# WaterSensor-V01-Build014.net
KiCad netlist of a schematic drawn in EAGLE
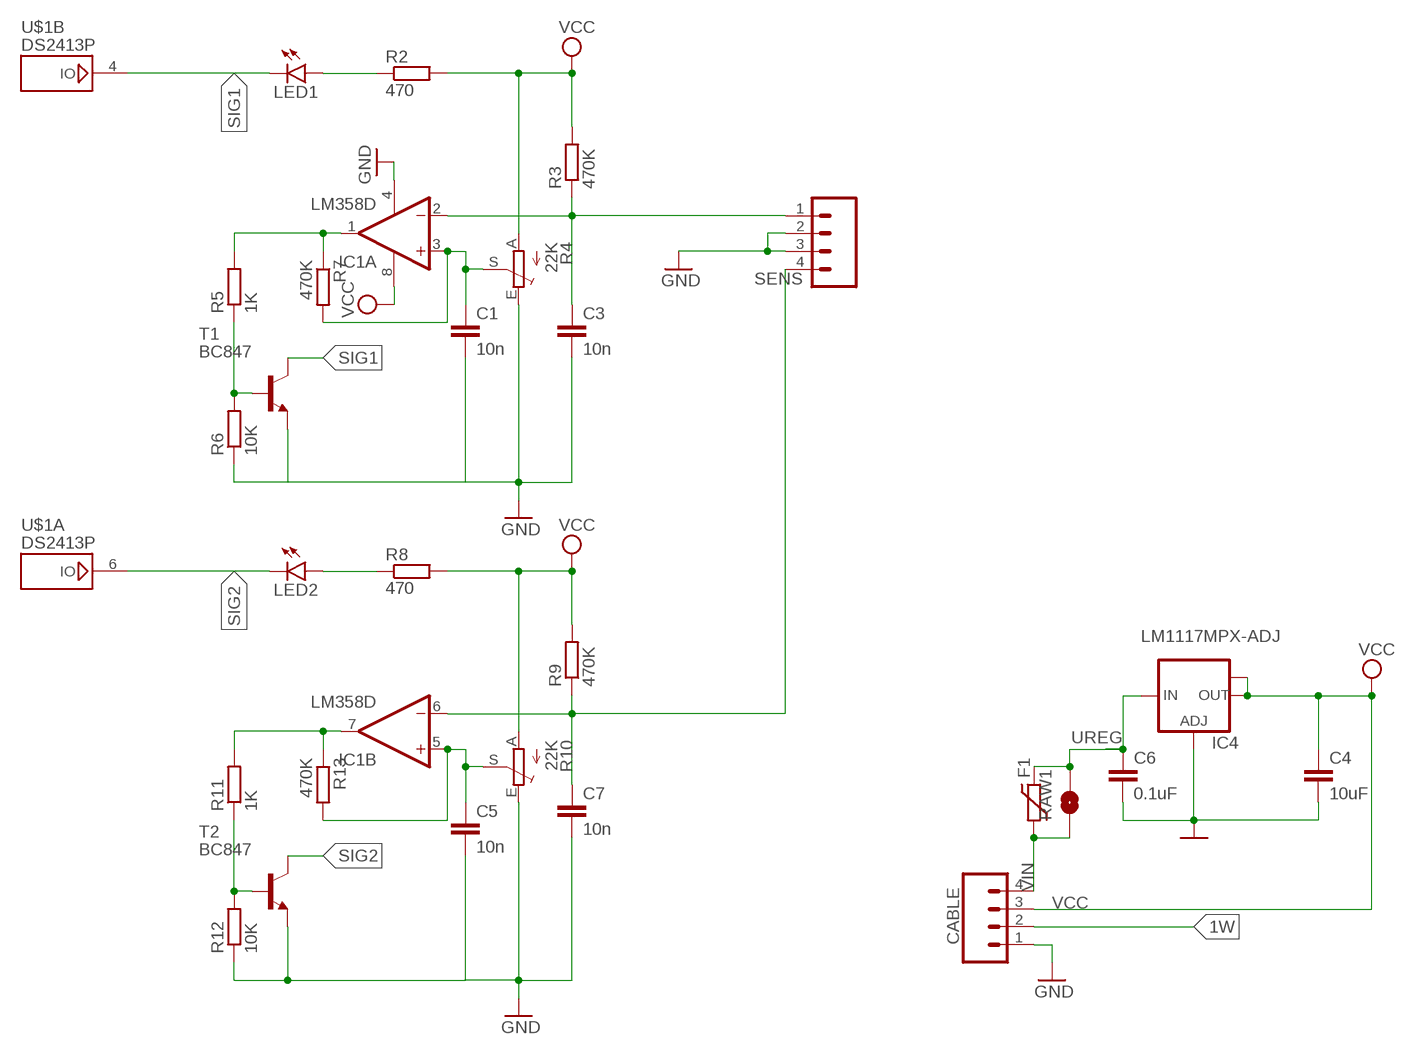
[diagram p0: schematic, sheet 1]

(export (version "E")
  (design (tool "Eeschema 10.0.6"))
  (components
    (comp (ref "C1")
      (value "10n")
      (footprint "eagle-import:C0805K")
      (libsource (lib "eagle-import") (part "rcl_334_C-EUC0805K"))
    )
    (comp (ref "C3")
      (value "10n")
      (footprint "eagle-import:C0805K")
      (libsource (lib "eagle-import") (part "rcl_334_C-EUC0805K"))
    )
    (comp (ref "C4")
      (value "10uF")
      (footprint "eagle-import:C1210")
      (libsource (lib "eagle-import") (part "C-EUC1210"))
    )
    (comp (ref "C5")
      (value "10n")
      (footprint "eagle-import:C0805K")
      (libsource (lib "eagle-import") (part "rcl_334_C-EUC0805K"))
    )
    (comp (ref "C6")
      (value "0.1uF")
      (footprint "eagle-import:C1206")
      (libsource (lib "eagle-import") (part "C-EUC1206"))
    )
    (comp (ref "C7")
      (value "10n")
      (footprint "eagle-import:C0805K")
      (libsource (lib "eagle-import") (part "rcl_334_C-EUC0805K"))
    )
    (comp (ref "CABLE")
      (value "CONN_04LONGPADS")
      (footprint "eagle-import:1X04_LONGPADS")
      (libsource (lib "eagle-import") (part "CONN_04LONGPADS"))
    )
    (comp (ref "F1")
      (value "1812L")
      (footprint "eagle-import:1812L")
      (libsource (lib "eagle-import") (part "1812L"))
    )
    (comp (ref "IC1")
      (value "LM358D")
      (footprint "eagle-import:SO08")
      (libsource (lib "eagle-import") (part "LM358D"))
    )
    (comp (ref "IC4")
      (value "LM1117MPX-ADJ")
      (footprint "eagle-import:SOT223")
      (libsource (lib "eagle-import") (part "LM1117MPX-ADJ"))
    )
    (comp (ref "LED1")
      (value "LEDCHIP-LED0805")
      (footprint "eagle-import:CHIP-LED0805")
      (libsource (lib "eagle-import") (part "LEDCHIP-LED0805"))
    )
    (comp (ref "LED2")
      (value "LEDCHIP-LED0805")
      (footprint "eagle-import:CHIP-LED0805")
      (libsource (lib "eagle-import") (part "LEDCHIP-LED0805"))
    )
    (comp (ref "R2")
      (value "470")
      (footprint "eagle-import:R0805W")
      (libsource (lib "eagle-import") (part "R-EU_R0805W"))
    )
    (comp (ref "R3")
      (value "470K")
      (footprint "eagle-import:R0805W")
      (libsource (lib "eagle-import") (part "R-EU_R0805W"))
    )
    (comp (ref "R4")
      (value "22K")
      (footprint "eagle-import:CA6V")
      (libsource (lib "eagle-import") (part "TRIM_EU-CA6V"))
    )
    (comp (ref "R5")
      (value "1K")
      (footprint "eagle-import:R0805W")
      (libsource (lib "eagle-import") (part "R-EU_R0805W"))
    )
    (comp (ref "R6")
      (value "10K")
      (footprint "eagle-import:R0805W")
      (libsource (lib "eagle-import") (part "R-EU_R0805W"))
    )
    (comp (ref "R7")
      (value "470K")
      (footprint "eagle-import:R0805W")
      (libsource (lib "eagle-import") (part "R-EU_R0805W"))
    )
    (comp (ref "R8")
      (value "470")
      (footprint "eagle-import:R0805W")
      (libsource (lib "eagle-import") (part "R-EU_R0805W"))
    )
    (comp (ref "R9")
      (value "470K")
      (footprint "eagle-import:R0805W")
      (libsource (lib "eagle-import") (part "R-EU_R0805W"))
    )
    (comp (ref "R10")
      (value "22K")
      (footprint "eagle-import:CA6V")
      (libsource (lib "eagle-import") (part "TRIM_EU-CA6V"))
    )
    (comp (ref "R11")
      (value "1K")
      (footprint "eagle-import:R0805W")
      (libsource (lib "eagle-import") (part "R-EU_R0805W"))
    )
    (comp (ref "R12")
      (value "10K")
      (footprint "eagle-import:R0805W")
      (libsource (lib "eagle-import") (part "R-EU_R0805W"))
    )
    (comp (ref "R13")
      (value "470K")
      (footprint "eagle-import:R0805W")
      (libsource (lib "eagle-import") (part "R-EU_R0805W"))
    )
    (comp (ref "RAW1")
      (value "JUMPER-SMT_2_NO_SILK")
      (footprint "eagle-import:SMT-JUMPER_2_NO_SILK")
      (libsource (lib "eagle-import") (part "JUMPER-SMT_2_NO_SILK"))
    )
    (comp (ref "SENS")
      (value "CONN_04LONGPADS")
      (footprint "eagle-import:1X04_LONGPADS")
      (libsource (lib "eagle-import") (part "CONN_04LONGPADS"))
    )
    (comp (ref "T1")
      (value "BC847")
      (footprint "eagle-import:SOT23")
      (libsource (lib "eagle-import") (part "BC847"))
    )
    (comp (ref "T2")
      (value "BC847")
      (footprint "eagle-import:SOT23")
      (libsource (lib "eagle-import") (part "BC847"))
    )
    (comp (ref "U$1")
      (value "DS2413P")
      (footprint "eagle-import:TSOC6")
      (libsource (lib "eagle-import") (part "DS2413P"))
    )
  )
  (nets
    (net (code "1") (name "/UREG") (class "Default")
      (node (ref "C6") (pin "1") (pinfunction "1_1") (pintype "passive"))
      (node (ref "F1") (pin "P$1") (pinfunction "1_P$1") (pintype "passive"))
      (node (ref "IC4") (pin "3") (pinfunction "IN_3") (pintype "input"))
      (node (ref "RAW1") (pin "2") (pinfunction "2_2") (pintype "passive"))
    )
    (net (code "2") (name "/VIN") (class "Default")
      (node (ref "CABLE") (pin "4") (pinfunction "4_4") (pintype "passive"))
      (node (ref "F1") (pin "P$2") (pinfunction "2_P$2") (pintype "passive"))
      (node (ref "RAW1") (pin "1") (pinfunction "1_1") (pintype "passive"))
    )
    (net (code "3") (name "1W") (class "Default")
      (node (ref "CABLE") (pin "2") (pinfunction "2_2") (pintype "passive"))
    )
    (net (code "4") (name "GND") (class "Default")
      (node (ref "C1") (pin "2") (pinfunction "2_2") (pintype "passive"))
      (node (ref "C3") (pin "2") (pinfunction "2_2") (pintype "passive"))
      (node (ref "C4") (pin "2") (pinfunction "2_2") (pintype "passive"))
      (node (ref "C5") (pin "2") (pinfunction "2_2") (pintype "passive"))
      (node (ref "C6") (pin "2") (pinfunction "2_2") (pintype "passive"))
      (node (ref "C7") (pin "2") (pinfunction "2_2") (pintype "passive"))
      (node (ref "CABLE") (pin "1") (pinfunction "1_1") (pintype "passive"))
      (node (ref "IC1") (pin "4") (pinfunction "V-_4") (pintype "power_in"))
      (node (ref "IC4") (pin "1") (pinfunction "ADJ_1") (pintype "input"))
      (node (ref "R10") (pin "E") (pinfunction "E_E") (pintype "passive"))
      (node (ref "R12") (pin "1") (pinfunction "1_1") (pintype "passive"))
      (node (ref "R4") (pin "E") (pinfunction "E_E") (pintype "passive"))
      (node (ref "R6") (pin "1") (pinfunction "1_1") (pintype "passive"))
      (node (ref "SENS") (pin "2") (pinfunction "2_2") (pintype "passive"))
      (node (ref "SENS") (pin "3") (pinfunction "3_3") (pintype "passive"))
      (node (ref "T1") (pin "2") (pinfunction "E_2") (pintype "passive"))
      (node (ref "T2") (pin "2") (pinfunction "E_2") (pintype "passive"))
    )
    (net (code "5") (name "Net-(IC1A-+IN)") (class "Default")
      (node (ref "C1") (pin "1") (pinfunction "1_1") (pintype "passive"))
      (node (ref "IC1") (pin "3") (pinfunction "+IN_3") (pintype "input"))
      (node (ref "R4") (pin "S") (pinfunction "S_S") (pintype "passive"))
      (node (ref "R7") (pin "2") (pinfunction "2_2") (pintype "passive"))
    )
    (net (code "6") (name "Net-(IC1A--IN)") (class "Default")
      (node (ref "C3") (pin "1") (pinfunction "1_1") (pintype "passive"))
      (node (ref "IC1") (pin "2") (pinfunction "-IN_2") (pintype "input"))
      (node (ref "R3") (pin "1") (pinfunction "1_1") (pintype "passive"))
      (node (ref "SENS") (pin "1") (pinfunction "1_1") (pintype "passive"))
    )
    (net (code "7") (name "Net-(IC1A-OUT)") (class "Default")
      (node (ref "IC1") (pin "1") (pinfunction "OUT_1") (pintype "output"))
      (node (ref "R5") (pin "2") (pinfunction "2_2") (pintype "passive"))
      (node (ref "R7") (pin "1") (pinfunction "1_1") (pintype "passive"))
    )
    (net (code "8") (name "Net-(IC1B-+IN)") (class "Default")
      (node (ref "C5") (pin "1") (pinfunction "1_1") (pintype "passive"))
      (node (ref "IC1") (pin "5") (pinfunction "+IN_5") (pintype "input"))
      (node (ref "R10") (pin "S") (pinfunction "S_S") (pintype "passive"))
      (node (ref "R13") (pin "2") (pinfunction "2_2") (pintype "passive"))
    )
    (net (code "9") (name "Net-(IC1B--IN)") (class "Default")
      (node (ref "C7") (pin "1") (pinfunction "1_1") (pintype "passive"))
      (node (ref "IC1") (pin "6") (pinfunction "-IN_6") (pintype "input"))
      (node (ref "R9") (pin "1") (pinfunction "1_1") (pintype "passive"))
      (node (ref "SENS") (pin "4") (pinfunction "4_4") (pintype "passive"))
    )
    (net (code "10") (name "Net-(IC1B-OUT)") (class "Default")
      (node (ref "IC1") (pin "7") (pinfunction "OUT_7") (pintype "output"))
      (node (ref "R11") (pin "2") (pinfunction "2_2") (pintype "passive"))
      (node (ref "R13") (pin "1") (pinfunction "1_1") (pintype "passive"))
    )
    (net (code "11") (name "Net-(LED1-PadA)") (class "Default")
      (node (ref "LED1") (pin "A") (pinfunction "A_A") (pintype "passive"))
      (node (ref "R2") (pin "1") (pinfunction "1_1") (pintype "passive"))
    )
    (net (code "12") (name "Net-(LED2-PadA)") (class "Default")
      (node (ref "LED2") (pin "A") (pinfunction "A_A") (pintype "passive"))
      (node (ref "R8") (pin "1") (pinfunction "1_1") (pintype "passive"))
    )
    (net (code "13") (name "Net-(T1-B)") (class "Default")
      (node (ref "R5") (pin "1") (pinfunction "1_1") (pintype "passive"))
      (node (ref "R6") (pin "2") (pinfunction "2_2") (pintype "passive"))
      (node (ref "T1") (pin "1") (pinfunction "B_1") (pintype "passive"))
    )
    (net (code "14") (name "Net-(T2-B)") (class "Default")
      (node (ref "R11") (pin "1") (pinfunction "1_1") (pintype "passive"))
      (node (ref "R12") (pin "2") (pinfunction "2_2") (pintype "passive"))
      (node (ref "T2") (pin "1") (pinfunction "B_1") (pintype "passive"))
    )
    (net (code "15") (name "SIG1") (class "Default")
      (node (ref "LED1") (pin "C") (pinfunction "C_C") (pintype "passive"))
      (node (ref "T1") (pin "3") (pinfunction "C_3") (pintype "passive"))
      (node (ref "U$1") (pin "4") (pinfunction "IO_4") (pintype "open_collector"))
    )
    (net (code "16") (name "SIG2") (class "Default")
      (node (ref "LED2") (pin "C") (pinfunction "C_C") (pintype "passive"))
      (node (ref "T2") (pin "3") (pinfunction "C_3") (pintype "passive"))
      (node (ref "U$1") (pin "6") (pinfunction "IO_6") (pintype "open_collector"))
    )
    (net (code "17") (name "VCC") (class "Default")
      (node (ref "C4") (pin "1") (pinfunction "1_1") (pintype "passive"))
      (node (ref "CABLE") (pin "3") (pinfunction "3_3") (pintype "passive"))
      (node (ref "IC1") (pin "8") (pinfunction "V+_8") (pintype "power_in"))
      (node (ref "IC4") (pin "2") (pinfunction "OUT_2") (pintype "passive"))
      (node (ref "IC4") (pin "TAB") (pinfunction "OUT1_TAB") (pintype "passive"))
      (node (ref "R10") (pin "A") (pinfunction "A_A") (pintype "passive"))
      (node (ref "R2") (pin "2") (pinfunction "2_2") (pintype "passive"))
      (node (ref "R3") (pin "2") (pinfunction "2_2") (pintype "passive"))
      (node (ref "R4") (pin "A") (pinfunction "A_A") (pintype "passive"))
      (node (ref "R8") (pin "2") (pinfunction "2_2") (pintype "passive"))
      (node (ref "R9") (pin "2") (pinfunction "2_2") (pintype "passive"))
    )
  )
)
